# MONITOR.net
KiCad netlist of a schematic drawn in Altium Designer
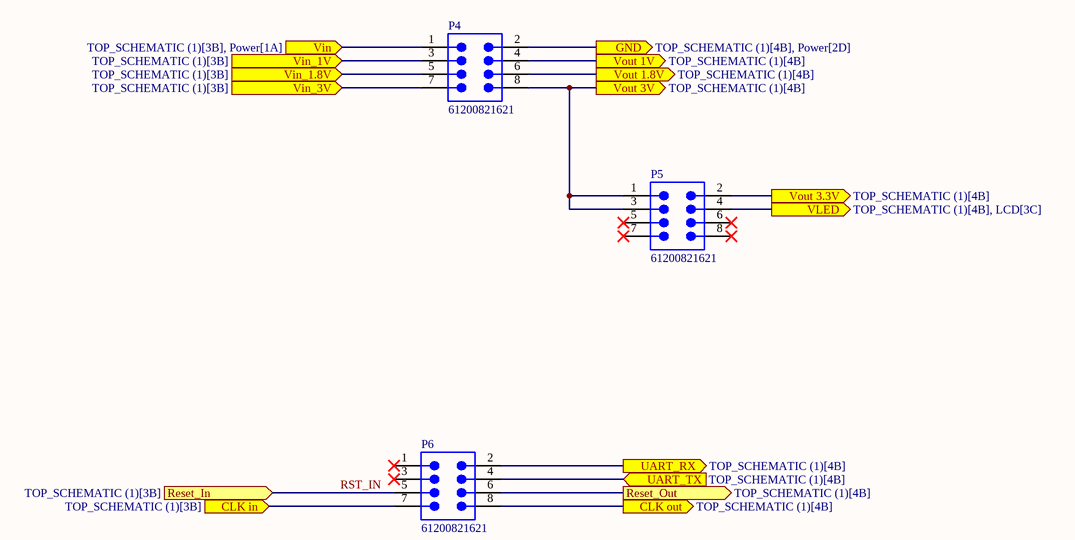
[diagram p0: MONITOR.SchDoc]

(export (version "E")
  (design (tool "Eeschema 10.0.6"))
  (components
    (comp (ref "P4")
      (value "61200821621")
      (footprint "61200821621")
      (description "Wr-bhd; 2.54MM Pitch 8 Way 2 Row Shrouded Straight Pcb Header, Surface Mount")
      (libsource (lib "Altium Content Vault") (part "Header_Male_2R_08P"))
    )
    (comp (ref "P5")
      (value "61200821621")
      (footprint "61200821621")
      (description "Wr-bhd; 2.54MM Pitch 8 Way 2 Row Shrouded Straight Pcb Header, Surface Mount")
      (libsource (lib "Altium Content Vault") (part "Header_Male_2R_08P"))
    )
    (comp (ref "P6")
      (value "61200821621")
      (footprint "61200821621")
      (description "Wr-bhd; 2.54MM Pitch 8 Way 2 Row Shrouded Straight Pcb Header, Surface Mount")
      (libsource (lib "Altium Content Vault") (part "Header_Male_2R_08P"))
    )
  )
  (nets
    (net (code "1") (name "/CLK in") (class "Default")
      (node (ref "P6") (pin "7") (pinfunction "7_7") (pintype "passive"))
    )
    (net (code "2") (name "/CLK out") (class "Default")
      (node (ref "P6") (pin "8") (pinfunction "8_8") (pintype "passive"))
    )
    (net (code "3") (name "/GND") (class "Default")
      (node (ref "P4") (pin "2") (pinfunction "2_2") (pintype "passive"))
    )
    (net (code "4") (name "/RST_IN") (class "Default")
      (node (ref "P6") (pin "5") (pinfunction "5_5") (pintype "passive"))
    )
    (net (code "5") (name "/Reset_Out") (class "Default")
      (node (ref "P6") (pin "6") (pinfunction "6_6") (pintype "passive"))
    )
    (net (code "6") (name "/UART_RX") (class "Default")
      (node (ref "P6") (pin "2") (pinfunction "2_2") (pintype "passive"))
    )
    (net (code "7") (name "/UART_TX") (class "Default")
      (node (ref "P6") (pin "4") (pinfunction "4_4") (pintype "passive"))
    )
    (net (code "8") (name "/VLED") (class "Default")
      (node (ref "P5") (pin "4") (pinfunction "4_4") (pintype "passive"))
    )
    (net (code "9") (name "/Vin") (class "Default")
      (node (ref "P4") (pin "1") (pinfunction "1_1") (pintype "passive"))
    )
    (net (code "10") (name "/Vin_1.8V") (class "Default")
      (node (ref "P4") (pin "5") (pinfunction "5_5") (pintype "passive"))
    )
    (net (code "11") (name "/Vin_1V") (class "Default")
      (node (ref "P4") (pin "3") (pinfunction "3_3") (pintype "passive"))
    )
    (net (code "12") (name "/Vin_3V") (class "Default")
      (node (ref "P4") (pin "7") (pinfunction "7_7") (pintype "passive"))
    )
    (net (code "13") (name "/Vout 1.8V") (class "Default")
      (node (ref "P4") (pin "6") (pinfunction "6_6") (pintype "passive"))
    )
    (net (code "14") (name "/Vout 1V") (class "Default")
      (node (ref "P4") (pin "4") (pinfunction "4_4") (pintype "passive"))
    )
    (net (code "15") (name "/Vout 3.3V") (class "Default")
      (node (ref "P5") (pin "2") (pinfunction "2_2") (pintype "passive"))
    )
    (net (code "16") (name "/Vout 3V") (class "Default")
      (node (ref "P4") (pin "8") (pinfunction "8_8") (pintype "passive"))
      (node (ref "P5") (pin "1") (pinfunction "1_1") (pintype "passive"))
      (node (ref "P5") (pin "3") (pinfunction "3_3") (pintype "passive"))
    )
    (net (code "17") (name "unconnected-(P5-Pad5)") (class "Default")
      (node (ref "P5") (pin "5") (pinfunction "5_5") (pintype "passive+no_connect"))
    )
    (net (code "18") (name "unconnected-(P5-Pad6)") (class "Default")
      (node (ref "P5") (pin "6") (pinfunction "6_6") (pintype "passive+no_connect"))
    )
    (net (code "19") (name "unconnected-(P5-Pad7)") (class "Default")
      (node (ref "P5") (pin "7") (pinfunction "7_7") (pintype "passive+no_connect"))
    )
    (net (code "20") (name "unconnected-(P5-Pad8)") (class "Default")
      (node (ref "P5") (pin "8") (pinfunction "8_8") (pintype "passive+no_connect"))
    )
    (net (code "21") (name "unconnected-(P6-Pad1)") (class "Default")
      (node (ref "P6") (pin "1") (pinfunction "1_1") (pintype "passive+no_connect"))
    )
    (net (code "22") (name "unconnected-(P6-Pad3)") (class "Default")
      (node (ref "P6") (pin "3") (pinfunction "3_3") (pintype "passive+no_connect"))
    )
  )
)
